# POWER.net
KiCad netlist of a schematic drawn in Altium Designer
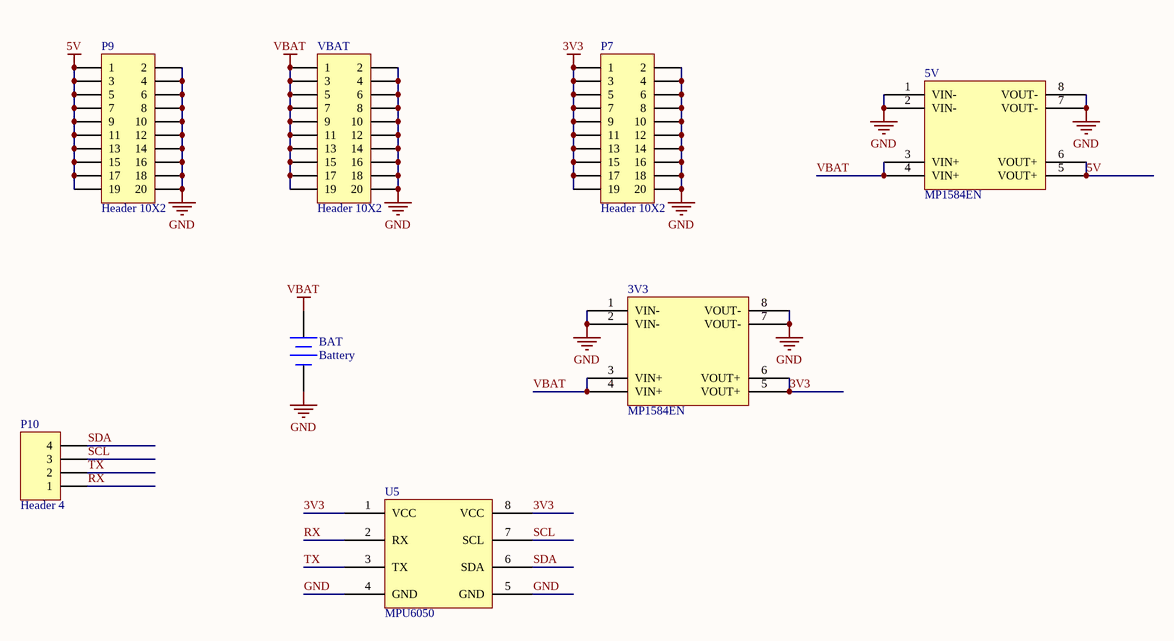
[diagram p0: POWER.SchDoc]

(export (version "E")
  (design (tool "Eeschema 10.0.6"))
  (components
    (comp (ref "3V3")
      (value "MP1584EN")
      (footprint "MP1584EN:PCBComponent_1")
      (libsource (lib "MP1584EN") (part "MP1584EN"))
    )
    (comp (ref "5V")
      (value "MP1584EN")
      (footprint "MP1584EN:PCBComponent_1")
      (libsource (lib "MP1584EN") (part "MP1584EN"))
    )
    (comp (ref "BAT")
      (value "Battery")
      (footprint "BAT-2")
      (description "Multicell Battery")
      (fields (field (name "PUBLISHER") "Altium Limited"))
      (libsource (lib "Miscellaneous Devices") (part "Battery"))
    )
    (comp (ref "P7")
      (value "Header 10X2")
      (footprint "HDR2X10")
      (description "Header, 10-Pin, Dual row")
      (fields (field (name "PUBLISHER") "Altium Limited"))
      (libsource (lib "Miscellaneous Connectors") (part "Header 10X2"))
    )
    (comp (ref "P9")
      (value "Header 10X2")
      (footprint "HDR2X10")
      (description "Header, 10-Pin, Dual row")
      (fields (field (name "PUBLISHER") "Altium Limited"))
      (libsource (lib "Miscellaneous Connectors") (part "Header 10X2"))
    )
    (comp (ref "P10")
      (value "Header 4")
      (footprint "HDR1X4")
      (description "Header, 4-Pin")
      (fields (field (name "PUBLISHER") "Altium Limited"))
      (libsource (lib "Miscellaneous Connectors") (part "Header 4"))
    )
    (comp (ref "U5") (value "MPU6050") (footprint "MPU6050") (libsource (lib "MPU6050") (part "MPU6050")))
    (comp (ref "VBAT")
      (value "Header 10X2")
      (footprint "HDR2X10")
      (description "Header, 10-Pin, Dual row")
      (fields (field (name "PUBLISHER") "Altium Limited"))
      (libsource (lib "Miscellaneous Connectors") (part "Header 10X2"))
    )
  )
  (nets
    (net (code "1") (name "/RX") (class "Default")
      (node (ref "P10") (pin "1") (pinfunction "1_1") (pintype "passive"))
      (node (ref "U5") (pin "2") (pinfunction "RX_2") (pintype "passive"))
    )
    (net (code "2") (name "/SCL") (class "Default")
      (node (ref "P10") (pin "3") (pinfunction "3_3") (pintype "passive"))
      (node (ref "U5") (pin "7") (pinfunction "SCL_7") (pintype "passive"))
    )
    (net (code "3") (name "/SDA") (class "Default")
      (node (ref "P10") (pin "4") (pinfunction "4_4") (pintype "passive"))
      (node (ref "U5") (pin "6") (pinfunction "SDA_6") (pintype "passive"))
    )
    (net (code "4") (name "/TX") (class "Default")
      (node (ref "P10") (pin "2") (pinfunction "2_2") (pintype "passive"))
      (node (ref "U5") (pin "3") (pinfunction "TX_3") (pintype "passive"))
    )
    (net (code "5") (name "3V3") (class "Default")
      (node (ref "3V3") (pin "5") (pinfunction "VOUT+_5") (pintype "passive"))
      (node (ref "3V3") (pin "6") (pinfunction "VOUT+_6") (pintype "passive"))
      (node (ref "P7") (pin "1") (pinfunction "1_1") (pintype "passive"))
      (node (ref "P7") (pin "11") (pinfunction "11_11") (pintype "passive"))
      (node (ref "P7") (pin "13") (pinfunction "13_13") (pintype "passive"))
      (node (ref "P7") (pin "15") (pinfunction "15_15") (pintype "passive"))
      (node (ref "P7") (pin "17") (pinfunction "17_17") (pintype "passive"))
      (node (ref "P7") (pin "19") (pinfunction "19_19") (pintype "passive"))
      (node (ref "P7") (pin "3") (pinfunction "3_3") (pintype "passive"))
      (node (ref "P7") (pin "5") (pinfunction "5_5") (pintype "passive"))
      (node (ref "P7") (pin "7") (pinfunction "7_7") (pintype "passive"))
      (node (ref "P7") (pin "9") (pinfunction "9_9") (pintype "passive"))
      (node (ref "U5") (pin "1") (pinfunction "VCC_1") (pintype "passive"))
      (node (ref "U5") (pin "8") (pinfunction "VCC_8") (pintype "passive"))
    )
    (net (code "6") (name "5V") (class "Default")
      (node (ref "5V") (pin "5") (pinfunction "VOUT+_5") (pintype "passive"))
      (node (ref "5V") (pin "6") (pinfunction "VOUT+_6") (pintype "passive"))
      (node (ref "P9") (pin "1") (pinfunction "1_1") (pintype "passive"))
      (node (ref "P9") (pin "11") (pinfunction "11_11") (pintype "passive"))
      (node (ref "P9") (pin "13") (pinfunction "13_13") (pintype "passive"))
      (node (ref "P9") (pin "15") (pinfunction "15_15") (pintype "passive"))
      (node (ref "P9") (pin "17") (pinfunction "17_17") (pintype "passive"))
      (node (ref "P9") (pin "19") (pinfunction "19_19") (pintype "passive"))
      (node (ref "P9") (pin "3") (pinfunction "3_3") (pintype "passive"))
      (node (ref "P9") (pin "5") (pinfunction "5_5") (pintype "passive"))
      (node (ref "P9") (pin "7") (pinfunction "7_7") (pintype "passive"))
      (node (ref "P9") (pin "9") (pinfunction "9_9") (pintype "passive"))
    )
    (net (code "7") (name "GND") (class "Default")
      (node (ref "3V3") (pin "1") (pinfunction "VIN-_1") (pintype "passive"))
      (node (ref "3V3") (pin "2") (pinfunction "VIN-_2") (pintype "passive"))
      (node (ref "3V3") (pin "7") (pinfunction "VOUT-_7") (pintype "passive"))
      (node (ref "3V3") (pin "8") (pinfunction "VOUT-_8") (pintype "passive"))
      (node (ref "5V") (pin "1") (pinfunction "VIN-_1") (pintype "passive"))
      (node (ref "5V") (pin "2") (pinfunction "VIN-_2") (pintype "passive"))
      (node (ref "5V") (pin "7") (pinfunction "VOUT-_7") (pintype "passive"))
      (node (ref "5V") (pin "8") (pinfunction "VOUT-_8") (pintype "passive"))
      (node (ref "BAT") (pin "2") (pinfunction "-_2") (pintype "passive"))
      (node (ref "P7") (pin "10") (pinfunction "10_10") (pintype "passive"))
      (node (ref "P7") (pin "12") (pinfunction "12_12") (pintype "passive"))
      (node (ref "P7") (pin "14") (pinfunction "14_14") (pintype "passive"))
      (node (ref "P7") (pin "16") (pinfunction "16_16") (pintype "passive"))
      (node (ref "P7") (pin "18") (pinfunction "18_18") (pintype "passive"))
      (node (ref "P7") (pin "2") (pinfunction "2_2") (pintype "passive"))
      (node (ref "P7") (pin "20") (pinfunction "20_20") (pintype "passive"))
      (node (ref "P7") (pin "4") (pinfunction "4_4") (pintype "passive"))
      (node (ref "P7") (pin "6") (pinfunction "6_6") (pintype "passive"))
      (node (ref "P7") (pin "8") (pinfunction "8_8") (pintype "passive"))
      (node (ref "P9") (pin "10") (pinfunction "10_10") (pintype "passive"))
      (node (ref "P9") (pin "12") (pinfunction "12_12") (pintype "passive"))
      (node (ref "P9") (pin "14") (pinfunction "14_14") (pintype "passive"))
      (node (ref "P9") (pin "16") (pinfunction "16_16") (pintype "passive"))
      (node (ref "P9") (pin "18") (pinfunction "18_18") (pintype "passive"))
      (node (ref "P9") (pin "2") (pinfunction "2_2") (pintype "passive"))
      (node (ref "P9") (pin "20") (pinfunction "20_20") (pintype "passive"))
      (node (ref "P9") (pin "4") (pinfunction "4_4") (pintype "passive"))
      (node (ref "P9") (pin "6") (pinfunction "6_6") (pintype "passive"))
      (node (ref "P9") (pin "8") (pinfunction "8_8") (pintype "passive"))
      (node (ref "U5") (pin "4") (pinfunction "GND_4") (pintype "passive"))
      (node (ref "U5") (pin "5") (pinfunction "GND_5") (pintype "passive"))
      (node (ref "VBAT") (pin "10") (pinfunction "10_10") (pintype "passive"))
      (node (ref "VBAT") (pin "12") (pinfunction "12_12") (pintype "passive"))
      (node (ref "VBAT") (pin "14") (pinfunction "14_14") (pintype "passive"))
      (node (ref "VBAT") (pin "16") (pinfunction "16_16") (pintype "passive"))
      (node (ref "VBAT") (pin "18") (pinfunction "18_18") (pintype "passive"))
      (node (ref "VBAT") (pin "2") (pinfunction "2_2") (pintype "passive"))
      (node (ref "VBAT") (pin "20") (pinfunction "20_20") (pintype "passive"))
      (node (ref "VBAT") (pin "4") (pinfunction "4_4") (pintype "passive"))
      (node (ref "VBAT") (pin "6") (pinfunction "6_6") (pintype "passive"))
      (node (ref "VBAT") (pin "8") (pinfunction "8_8") (pintype "passive"))
    )
    (net (code "8") (name "VBAT") (class "Default")
      (node (ref "3V3") (pin "3") (pinfunction "VIN+_3") (pintype "passive"))
      (node (ref "3V3") (pin "4") (pinfunction "VIN+_4") (pintype "passive"))
      (node (ref "5V") (pin "3") (pinfunction "VIN+_3") (pintype "passive"))
      (node (ref "5V") (pin "4") (pinfunction "VIN+_4") (pintype "passive"))
      (node (ref "BAT") (pin "1") (pinfunction "+_1") (pintype "passive"))
      (node (ref "VBAT") (pin "1") (pinfunction "1_1") (pintype "passive"))
      (node (ref "VBAT") (pin "11") (pinfunction "11_11") (pintype "passive"))
      (node (ref "VBAT") (pin "13") (pinfunction "13_13") (pintype "passive"))
      (node (ref "VBAT") (pin "15") (pinfunction "15_15") (pintype "passive"))
      (node (ref "VBAT") (pin "17") (pinfunction "17_17") (pintype "passive"))
      (node (ref "VBAT") (pin "19") (pinfunction "19_19") (pintype "passive"))
      (node (ref "VBAT") (pin "3") (pinfunction "3_3") (pintype "passive"))
      (node (ref "VBAT") (pin "5") (pinfunction "5_5") (pintype "passive"))
      (node (ref "VBAT") (pin "7") (pinfunction "7_7") (pintype "passive"))
      (node (ref "VBAT") (pin "9") (pinfunction "9_9") (pintype "passive"))
    )
  )
)
